# HorizBallCounter.net
KiCad netlist of a schematic drawn in Altium Designer
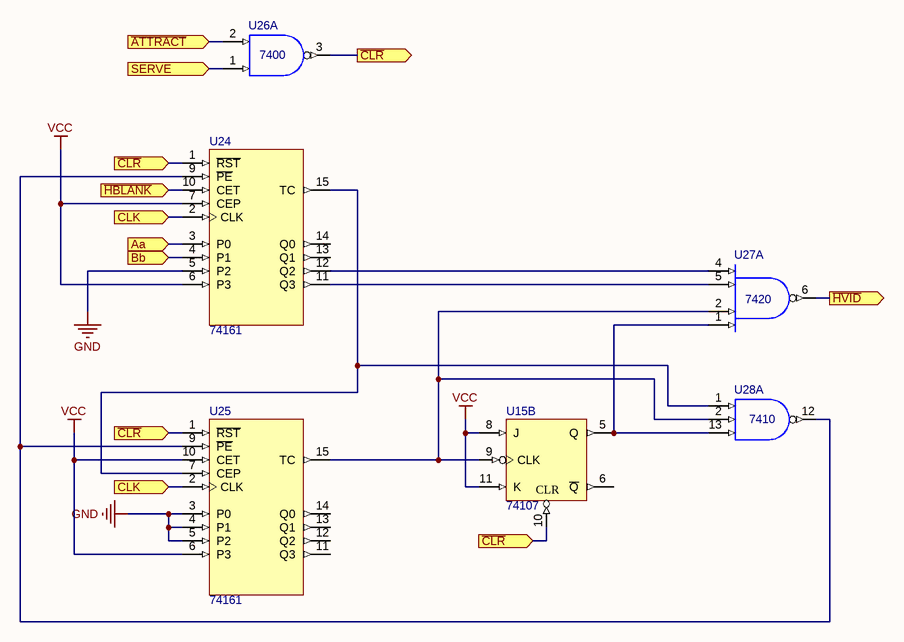
[diagram p0: HorizBallCounter.SchDoc]

(export (version "E")
  (design (tool "Eeschema 10.0.6"))
  (components
    (comp (ref "U15")
      (value "74107")
      (footprint "N014")
      (description "Dual J-K Flip-Flop with Clear")
      (fields (field (name "PUBLISHER") "Altium Limited"))
      (libsource (lib "TI Logic Flip-Flop") (part "SN74LS107AN"))
    )
    (comp (ref "U24")
      (value "74161")
      (footprint "N016")
      (description "Synchronous 4-Bit Counter")
      (fields (field (name "PUBLISHER") "Altium Limited"))
      (libsource (lib "TI Logic Counter") (part "SN74LS161AN"))
    )
    (comp (ref "U25")
      (value "74161")
      (footprint "N016")
      (description "Synchronous 4-Bit Counter")
      (fields (field (name "PUBLISHER") "Altium Limited"))
      (libsource (lib "TI Logic Counter") (part "SN74LS161AN"))
    )
    (comp (ref "U26")
      (value "7400")
      (footprint "N014")
      (description "Quadruple 2-Input Positive-NAND Gate")
      (fields (field (name "PUBLISHER") "Altium Limited"))
      (libsource (lib "TI Logic Gate 2") (part "SN74LS00N"))
    )
    (comp (ref "U27")
      (value "7420")
      (footprint "N014")
      (description "Dual 4-Input Positive-NAND Gate")
      (fields (field (name "PUBLISHER") "Altium Limited"))
      (libsource (lib "TI Logic Gate 2") (part "SN74LS20N"))
    )
    (comp (ref "U28")
      (value "7410")
      (footprint "N014")
      (description "Triple 3-Input Positive-NAND Gate")
      (fields (field (name "PUBLISHER") "Altium Limited"))
      (libsource (lib "TI Logic Gate 2") (part "SN74LS10N"))
    )
  )
  (nets
    (net (code "1") (name "/ATTRACT") (class "Default")
      (node (ref "U26") (pin "2") (pinfunction "B_2") (pintype "input"))
    )
    (net (code "2") (name "/Aa") (class "Default")
      (node (ref "U24") (pin "3") (pinfunction "P0_3") (pintype "input"))
    )
    (net (code "3") (name "/Bb") (class "Default")
      (node (ref "U24") (pin "4") (pinfunction "P1_4") (pintype "input"))
    )
    (net (code "4") (name "/CLK") (class "Default")
      (node (ref "U24") (pin "2") (pinfunction "CLK_2") (pintype "input"))
      (node (ref "U25") (pin "2") (pinfunction "CLK_2") (pintype "input"))
    )
    (net (code "5") (name "/CLR") (class "Default")
      (node (ref "U15") (pin "10") (pinfunction "CLR_10") (pintype "input"))
      (node (ref "U24") (pin "1") (pinfunction "~{RST}_1") (pintype "input"))
      (node (ref "U25") (pin "1") (pinfunction "~{RST}_1") (pintype "input"))
      (node (ref "U26") (pin "3") (pinfunction "Y_3") (pintype "output"))
    )
    (net (code "6") (name "/HBLANK") (class "Default")
      (node (ref "U24") (pin "10") (pinfunction "CET_10") (pintype "input"))
    )
    (net (code "7") (name "/HVID") (class "Default")
      (node (ref "U27") (pin "6") (pinfunction "Y_6") (pintype "output"))
    )
    (net (code "8") (name "/SERVE") (class "Default")
      (node (ref "U26") (pin "1") (pinfunction "A_1") (pintype "input"))
    )
    (net (code "9") (name "GND") (class "Default")
      (node (ref "U15") (pin "7") (pinfunction "GND_7") (pintype "power_in"))
      (node (ref "U24") (pin "5") (pinfunction "P2_5") (pintype "input"))
      (node (ref "U24") (pin "8") (pinfunction "GND_8") (pintype "power_in"))
      (node (ref "U25") (pin "3") (pinfunction "P0_3") (pintype "input"))
      (node (ref "U25") (pin "4") (pinfunction "P1_4") (pintype "input"))
      (node (ref "U25") (pin "5") (pinfunction "P2_5") (pintype "input"))
      (node (ref "U25") (pin "8") (pinfunction "GND_8") (pintype "power_in"))
      (node (ref "U26") (pin "7") (pinfunction "GND_7") (pintype "power_in"))
      (node (ref "U27") (pin "7") (pinfunction "GND_7") (pintype "power_in"))
      (node (ref "U28") (pin "7") (pinfunction "GND_7") (pintype "power_in"))
    )
    (net (code "10") (name "Net-(U15B-CLK)") (class "Default")
      (node (ref "U15") (pin "9") (pinfunction "CLK_9") (pintype "input"))
      (node (ref "U25") (pin "15") (pinfunction "TC_15") (pintype "output"))
      (node (ref "U27") (pin "2") (pinfunction "B_2") (pintype "input"))
      (node (ref "U28") (pin "2") (pinfunction "B_2") (pintype "input"))
    )
    (net (code "11") (name "Net-(U15B-Q)") (class "Default")
      (node (ref "U15") (pin "5") (pinfunction "Q_5") (pintype "output"))
      (node (ref "U27") (pin "1") (pinfunction "A_1") (pintype "input"))
      (node (ref "U28") (pin "13") (pinfunction "C_13") (pintype "input"))
    )
    (net (code "12") (name "Net-(U24-Q2)") (class "Default")
      (node (ref "U24") (pin "12") (pinfunction "Q2_12") (pintype "output"))
      (node (ref "U27") (pin "4") (pinfunction "C_4") (pintype "input"))
    )
    (net (code "13") (name "Net-(U24-Q3)") (class "Default")
      (node (ref "U24") (pin "11") (pinfunction "Q3_11") (pintype "output"))
      (node (ref "U27") (pin "5") (pinfunction "D_5") (pintype "input"))
    )
    (net (code "14") (name "Net-(U24-TC)") (class "Default")
      (node (ref "U24") (pin "15") (pinfunction "TC_15") (pintype "output"))
      (node (ref "U25") (pin "7") (pinfunction "CEP_7") (pintype "input"))
      (node (ref "U28") (pin "1") (pinfunction "A_1") (pintype "input"))
    )
    (net (code "15") (name "Net-(U24-~{PE})") (class "Default")
      (node (ref "U24") (pin "9") (pinfunction "~{PE}_9") (pintype "input"))
      (node (ref "U25") (pin "9") (pinfunction "~{PE}_9") (pintype "input"))
      (node (ref "U28") (pin "12") (pinfunction "Y_12") (pintype "output"))
    )
    (net (code "16") (name "VCC") (class "Default")
      (node (ref "U15") (pin "11") (pinfunction "K_11") (pintype "input"))
      (node (ref "U15") (pin "14") (pinfunction "VCC_14") (pintype "power_in"))
      (node (ref "U15") (pin "8") (pinfunction "J_8") (pintype "input"))
      (node (ref "U24") (pin "16") (pinfunction "VCC_16") (pintype "power_in"))
      (node (ref "U24") (pin "6") (pinfunction "P3_6") (pintype "input"))
      (node (ref "U24") (pin "7") (pinfunction "CEP_7") (pintype "input"))
      (node (ref "U25") (pin "10") (pinfunction "CET_10") (pintype "input"))
      (node (ref "U25") (pin "16") (pinfunction "VCC_16") (pintype "power_in"))
      (node (ref "U25") (pin "6") (pinfunction "P3_6") (pintype "input"))
      (node (ref "U26") (pin "14") (pinfunction "VCC_14") (pintype "power_in"))
      (node (ref "U27") (pin "14") (pinfunction "VCC_14") (pintype "power_in"))
      (node (ref "U28") (pin "14") (pinfunction "VCC_14") (pintype "power_in"))
    )
    (net (code "17") (name "unconnected-(U15B-~{Q}-Pad6)") (class "Default")
      (node (ref "U15") (pin "6") (pinfunction "~{Q}_6") (pintype "output"))
    )
    (net (code "18") (name "unconnected-(U24-Q0-Pad14)") (class "Default")
      (node (ref "U24") (pin "14") (pinfunction "Q0_14") (pintype "output"))
    )
    (net (code "19") (name "unconnected-(U24-Q1-Pad13)") (class "Default")
      (node (ref "U24") (pin "13") (pinfunction "Q1_13") (pintype "output"))
    )
    (net (code "20") (name "unconnected-(U25-Q0-Pad14)") (class "Default")
      (node (ref "U25") (pin "14") (pinfunction "Q0_14") (pintype "output"))
    )
    (net (code "21") (name "unconnected-(U25-Q1-Pad13)") (class "Default")
      (node (ref "U25") (pin "13") (pinfunction "Q1_13") (pintype "output"))
    )
    (net (code "22") (name "unconnected-(U25-Q2-Pad12)") (class "Default")
      (node (ref "U25") (pin "12") (pinfunction "Q2_12") (pintype "output"))
    )
    (net (code "23") (name "unconnected-(U25-Q3-Pad11)") (class "Default")
      (node (ref "U25") (pin "11") (pinfunction "Q3_11") (pintype "output"))
    )
  )
)
